# Node.net
KiCad netlist of a schematic drawn in Altium Designer
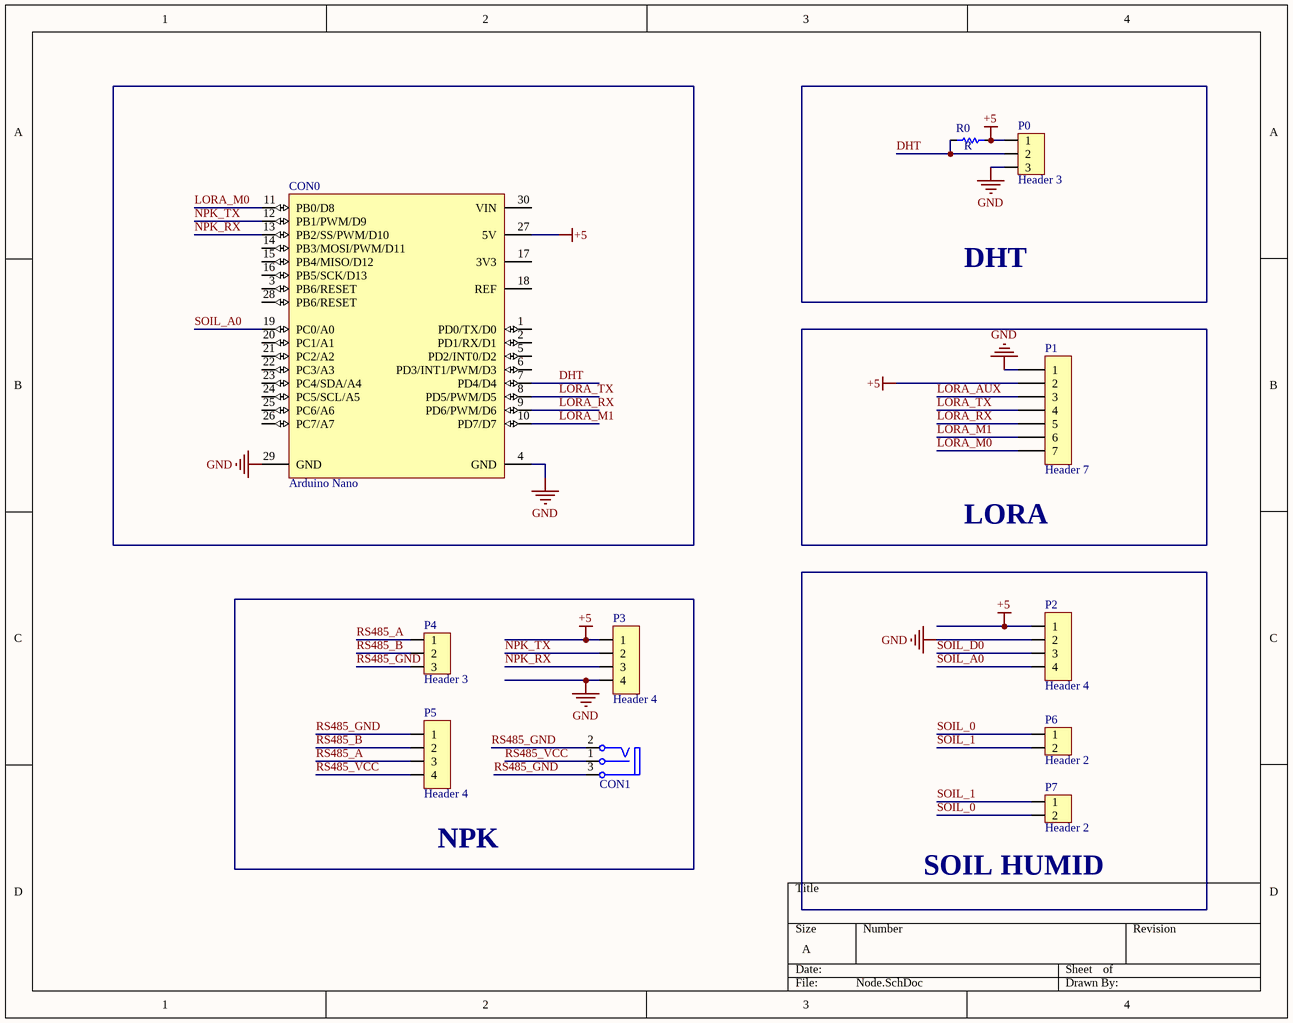
[diagram p0: Node.SchDoc]

(export (version "E")
  (design (tool "Eeschema 10.0.6"))
  (components
    (comp (ref "CON0")
      (value "Arduino Nano")
      (footprint "Arduino Nano 15x2")
      (description "Arduino Nano 15X2")
      (libsource (lib "BKIT4U_LIB_NEW") (part "Arduino Nano"))
    )
    (comp (ref "CON1")
      (value "CON DC PWR")
      (footprint "CONN/DC/PWR/5.0MM")
      (description "DC input connector")
      (libsource (lib "chipfc_altium_libs") (part "CON DC PWR"))
    )
    (comp (ref "P0")
      (value "Header 3")
      (footprint "XH2.54-3P")
      (description "Header, 3-Pin")
      (libsource (lib "BKIT4U_LIB_NEW") (part "Header 3"))
    )
    (comp (ref "P1")
      (value "Header 7")
      (footprint "Header 7")
      (description "Header, 7-Pin")
      (fields (field (name "PUBLISHER") "Altium Limited"))
      (libsource (lib "BKIT4U_LIB_NEW") (part "Header 7"))
    )
    (comp (ref "P2")
      (value "Header 4")
      (footprint "Header 4")
      (description "Header, 4-Pin")
      (libsource (lib "BKIT4U_LIB_NEW") (part "Header 4"))
    )
    (comp (ref "P3")
      (value "Header 4")
      (footprint "Header 4")
      (description "Header, 4-Pin")
      (libsource (lib "BKIT4U_LIB_NEW") (part "Header 4"))
    )
    (comp (ref "P4")
      (value "Header 3")
      (footprint "SH152-5.08-3P")
      (description "Header, 3-Pin")
      (libsource (lib "BKIT4U_LIB_NEW") (part "Header 3"))
    )
    (comp (ref "P5")
      (value "Header 4")
      (footprint "HDR DOMINO 4")
      (description "Header, 4-Pin")
      (libsource (lib "BKIT4U_LIB_NEW") (part "Header 4"))
    )
    (comp (ref "P6")
      (value "Header 2")
      (footprint "Header 2")
      (description "Header, 2-Pin")
      (fields (field (name "PUBLISHER") "Altium Limited"))
      (libsource (lib "BKIT4U_LIB_NEW") (part "Header 2"))
    )
    (comp (ref "P7")
      (value "Header 2")
      (footprint "XH2.54-2P")
      (description "Header, 2-Pin")
      (fields (field (name "PUBLISHER") "Altium Limited"))
      (libsource (lib "BKIT4U_LIB_NEW") (part "Header 2"))
    )
    (comp (ref "R0")
      (value "R")
      (footprint "R 1206 (3216)")
      (description "Resistor")
      (fields (field (name "PUBLISHER") "Altium Limited"))
      (libsource (lib "BKIT4U_LIB_NEW") (part "Resistor"))
    )
  )
  (nets
    (net (code "1") (name "+5") (class "Default")
      (node (ref "CON0") (pin "27") (pinfunction "5V_27") (pintype "power_in"))
      (node (ref "P0") (pin "1") (pinfunction "1_1") (pintype "passive"))
      (node (ref "P1") (pin "2") (pinfunction "2_2") (pintype "passive"))
      (node (ref "P2") (pin "1") (pinfunction "1_1") (pintype "passive"))
      (node (ref "P3") (pin "1") (pinfunction "1_1") (pintype "passive"))
      (node (ref "R0") (pin "2") (pinfunction "2_2") (pintype "passive"))
    )
    (net (code "2") (name "/DHT") (class "Default")
      (node (ref "CON0") (pin "7") (pinfunction "PD4/D4_7") (pintype "bidirectional"))
      (node (ref "P0") (pin "2") (pinfunction "2_2") (pintype "passive"))
      (node (ref "R0") (pin "1") (pinfunction "1_1") (pintype "passive"))
    )
    (net (code "3") (name "/LORA_AUX") (class "Default")
      (node (ref "P1") (pin "3") (pinfunction "3_3") (pintype "passive"))
    )
    (net (code "4") (name "/LORA_M0") (class "Default")
      (node (ref "CON0") (pin "11") (pinfunction "PB0/D8_11") (pintype "bidirectional"))
      (node (ref "P1") (pin "7") (pinfunction "7_7") (pintype "passive"))
    )
    (net (code "5") (name "/LORA_M1") (class "Default")
      (node (ref "CON0") (pin "10") (pinfunction "PD7/D7_10") (pintype "bidirectional"))
      (node (ref "P1") (pin "6") (pinfunction "6_6") (pintype "passive"))
    )
    (net (code "6") (name "/LORA_RX") (class "Default")
      (node (ref "CON0") (pin "9") (pinfunction "PD6/PWM/D6_9") (pintype "bidirectional"))
      (node (ref "P1") (pin "5") (pinfunction "5_5") (pintype "passive"))
    )
    (net (code "7") (name "/LORA_TX") (class "Default")
      (node (ref "CON0") (pin "8") (pinfunction "PD5/PWM/D5_8") (pintype "bidirectional"))
      (node (ref "P1") (pin "4") (pinfunction "4_4") (pintype "passive"))
    )
    (net (code "8") (name "/NPK_RX") (class "Default")
      (node (ref "CON0") (pin "13") (pinfunction "PB2/SS/PWM/D10_13") (pintype "bidirectional"))
      (node (ref "P3") (pin "3") (pinfunction "3_3") (pintype "passive"))
    )
    (net (code "9") (name "/NPK_TX") (class "Default")
      (node (ref "CON0") (pin "12") (pinfunction "PB1/PWM/D9_12") (pintype "bidirectional"))
      (node (ref "P3") (pin "2") (pinfunction "2_2") (pintype "passive"))
    )
    (net (code "10") (name "/RS485_A") (class "Default")
      (node (ref "P4") (pin "1") (pinfunction "1_1") (pintype "passive"))
      (node (ref "P5") (pin "3") (pinfunction "3_3") (pintype "passive"))
    )
    (net (code "11") (name "/RS485_B") (class "Default")
      (node (ref "P4") (pin "2") (pinfunction "2_2") (pintype "passive"))
      (node (ref "P5") (pin "2") (pinfunction "2_2") (pintype "passive"))
    )
    (net (code "12") (name "/RS485_GND") (class "Default")
      (node (ref "CON1") (pin "2") (pinfunction "T_2") (pintype "passive"))
      (node (ref "CON1") (pin "3") (pinfunction "TN_3") (pintype "passive"))
      (node (ref "P4") (pin "3") (pinfunction "3_3") (pintype "passive"))
      (node (ref "P5") (pin "1") (pinfunction "1_1") (pintype "passive"))
    )
    (net (code "13") (name "/RS485_VCC") (class "Default")
      (node (ref "CON1") (pin "1") (pinfunction "S_1") (pintype "power_in"))
      (node (ref "P5") (pin "4") (pinfunction "4_4") (pintype "passive"))
    )
    (net (code "14") (name "/SOIL_0") (class "Default")
      (node (ref "P6") (pin "1") (pinfunction "1_1") (pintype "passive"))
      (node (ref "P7") (pin "2") (pinfunction "2_2") (pintype "passive"))
    )
    (net (code "15") (name "/SOIL_1") (class "Default")
      (node (ref "P6") (pin "2") (pinfunction "2_2") (pintype "passive"))
      (node (ref "P7") (pin "1") (pinfunction "1_1") (pintype "passive"))
    )
    (net (code "16") (name "/SOIL_A0") (class "Default")
      (node (ref "CON0") (pin "19") (pinfunction "PC0/A0_19") (pintype "bidirectional"))
      (node (ref "P2") (pin "4") (pinfunction "4_4") (pintype "passive"))
    )
    (net (code "17") (name "/SOIL_D0") (class "Default")
      (node (ref "P2") (pin "3") (pinfunction "3_3") (pintype "passive"))
    )
    (net (code "18") (name "GND") (class "Default")
      (node (ref "CON0") (pin "29") (pinfunction "GND_29") (pintype "power_in"))
      (node (ref "CON0") (pin "4") (pinfunction "GND_4") (pintype "power_in"))
      (node (ref "P0") (pin "3") (pinfunction "3_3") (pintype "passive"))
      (node (ref "P1") (pin "1") (pinfunction "1_1") (pintype "passive"))
      (node (ref "P2") (pin "2") (pinfunction "2_2") (pintype "passive"))
      (node (ref "P3") (pin "4") (pinfunction "4_4") (pintype "passive"))
    )
    (net (code "19") (name "unconnected-(CON0-3V3-Pad17)") (class "Default")
      (node (ref "CON0") (pin "17") (pinfunction "3V3_17") (pintype "power_in"))
    )
    (net (code "20") (name "unconnected-(CON0-PB3{slash}MOSI{slash}PWM{slash}D11-Pad14)") (class "Default")
      (node (ref "CON0") (pin "14") (pinfunction "PB3/MOSI/PWM/D11_14") (pintype "bidirectional"))
    )
    (net (code "21") (name "unconnected-(CON0-PB4{slash}MISO{slash}D12-Pad15)") (class "Default")
      (node (ref "CON0") (pin "15") (pinfunction "PB4/MISO/D12_15") (pintype "bidirectional"))
    )
    (net (code "22") (name "unconnected-(CON0-PB5{slash}SCK{slash}D13-Pad16)") (class "Default")
      (node (ref "CON0") (pin "16") (pinfunction "PB5/SCK/D13_16") (pintype "bidirectional"))
    )
    (net (code "23") (name "unconnected-(CON0-PB6{slash}RESET-Pad3)") (class "Default")
      (node (ref "CON0") (pin "3") (pinfunction "PB6/RESET_3") (pintype "bidirectional"))
    )
    (net (code "24") (name "unconnected-(CON0-PB6{slash}RESET-Pad28)") (class "Default")
      (node (ref "CON0") (pin "28") (pinfunction "PB6/RESET_28") (pintype "bidirectional"))
    )
    (net (code "25") (name "unconnected-(CON0-PC1{slash}A1-Pad20)") (class "Default")
      (node (ref "CON0") (pin "20") (pinfunction "PC1/A1_20") (pintype "bidirectional"))
    )
    (net (code "26") (name "unconnected-(CON0-PC2{slash}A2-Pad21)") (class "Default")
      (node (ref "CON0") (pin "21") (pinfunction "PC2/A2_21") (pintype "bidirectional"))
    )
    (net (code "27") (name "unconnected-(CON0-PC3{slash}A3-Pad22)") (class "Default")
      (node (ref "CON0") (pin "22") (pinfunction "PC3/A3_22") (pintype "bidirectional"))
    )
    (net (code "28") (name "unconnected-(CON0-PC4{slash}SDA{slash}A4-Pad23)") (class "Default")
      (node (ref "CON0") (pin "23") (pinfunction "PC4/SDA/A4_23") (pintype "bidirectional"))
    )
    (net (code "29") (name "unconnected-(CON0-PC5{slash}SCL{slash}A5-Pad24)") (class "Default")
      (node (ref "CON0") (pin "24") (pinfunction "PC5/SCL/A5_24") (pintype "bidirectional"))
    )
    (net (code "30") (name "unconnected-(CON0-PC6{slash}A6-Pad25)") (class "Default")
      (node (ref "CON0") (pin "25") (pinfunction "PC6/A6_25") (pintype "bidirectional"))
    )
    (net (code "31") (name "unconnected-(CON0-PC7{slash}A7-Pad26)") (class "Default")
      (node (ref "CON0") (pin "26") (pinfunction "PC7/A7_26") (pintype "bidirectional"))
    )
    (net (code "32") (name "unconnected-(CON0-PD0{slash}TX{slash}D0-Pad1)") (class "Default")
      (node (ref "CON0") (pin "1") (pinfunction "PD0/TX/D0_1") (pintype "bidirectional"))
    )
    (net (code "33") (name "unconnected-(CON0-PD1{slash}RX{slash}D1-Pad2)") (class "Default")
      (node (ref "CON0") (pin "2") (pinfunction "PD1/RX/D1_2") (pintype "bidirectional"))
    )
    (net (code "34") (name "unconnected-(CON0-PD2{slash}INT0{slash}D2-Pad5)") (class "Default")
      (node (ref "CON0") (pin "5") (pinfunction "PD2/INT0/D2_5") (pintype "bidirectional"))
    )
    (net (code "35") (name "unconnected-(CON0-PD3{slash}INT1{slash}PWM{slash}D3-Pad6)") (class "Default")
      (node (ref "CON0") (pin "6") (pinfunction "PD3/INT1/PWM/D3_6") (pintype "bidirectional"))
    )
    (net (code "36") (name "unconnected-(CON0-REF-Pad18)") (class "Default")
      (node (ref "CON0") (pin "18") (pinfunction "REF_18") (pintype "power_in"))
    )
    (net (code "37") (name "unconnected-(CON0-VIN-Pad30)") (class "Default")
      (node (ref "CON0") (pin "30") (pinfunction "VIN_30") (pintype "power_in"))
    )
  )
)
